# e-stop-radio.net
KiCad netlist of a schematic drawn in EAGLE
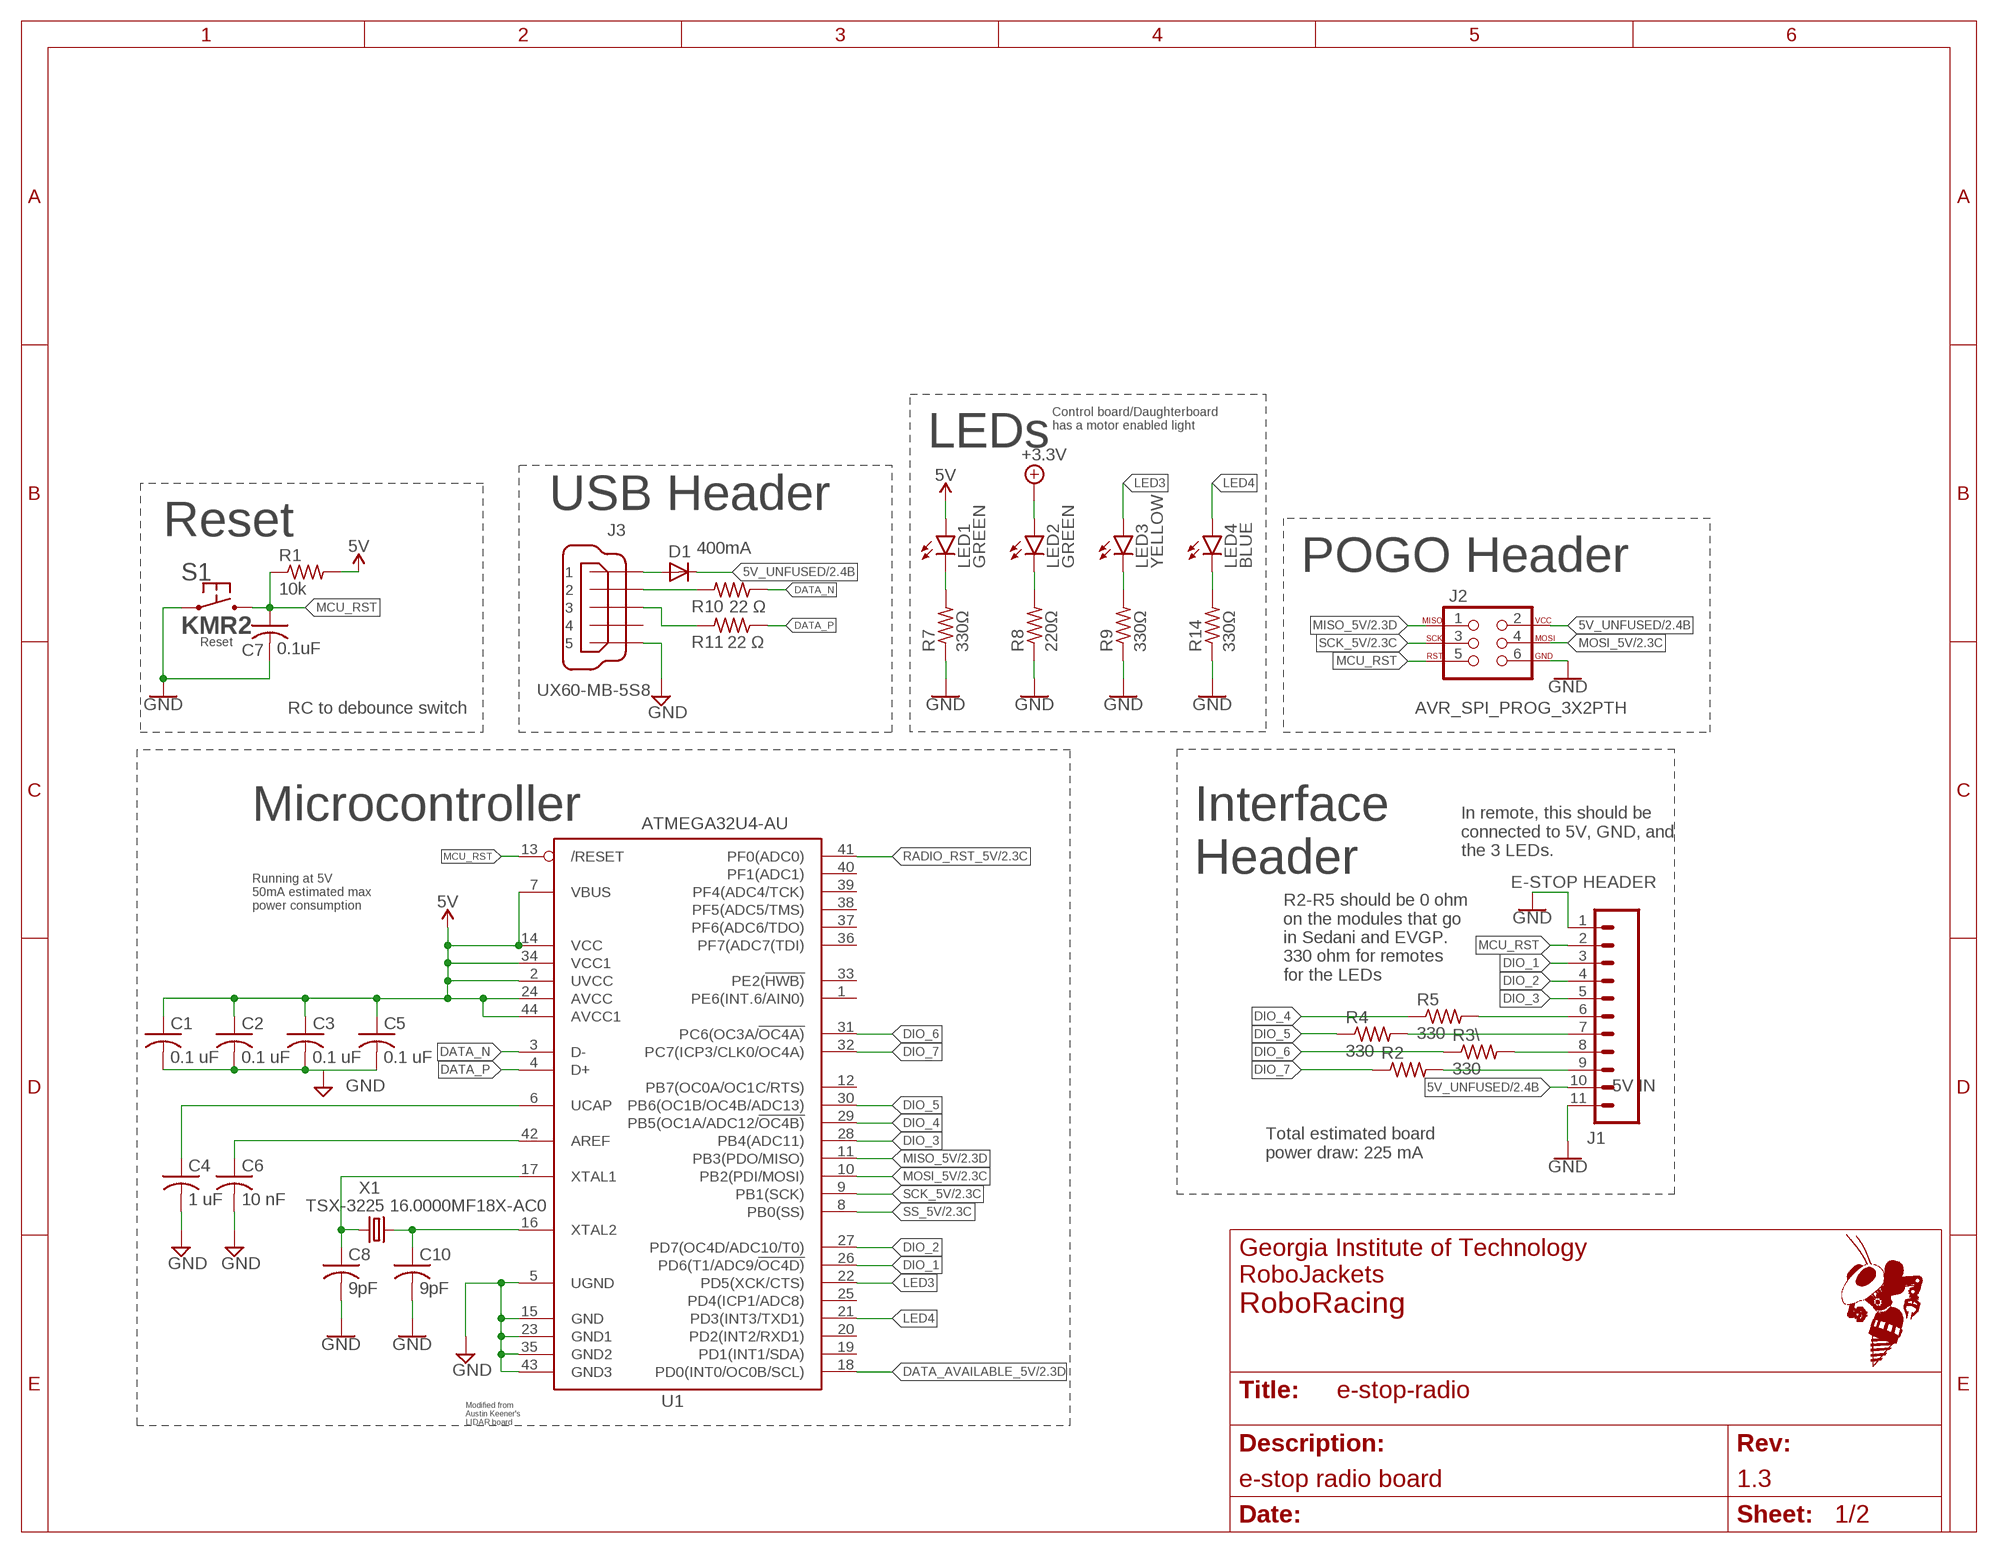
[diagram p0: schematic, sheet 1]
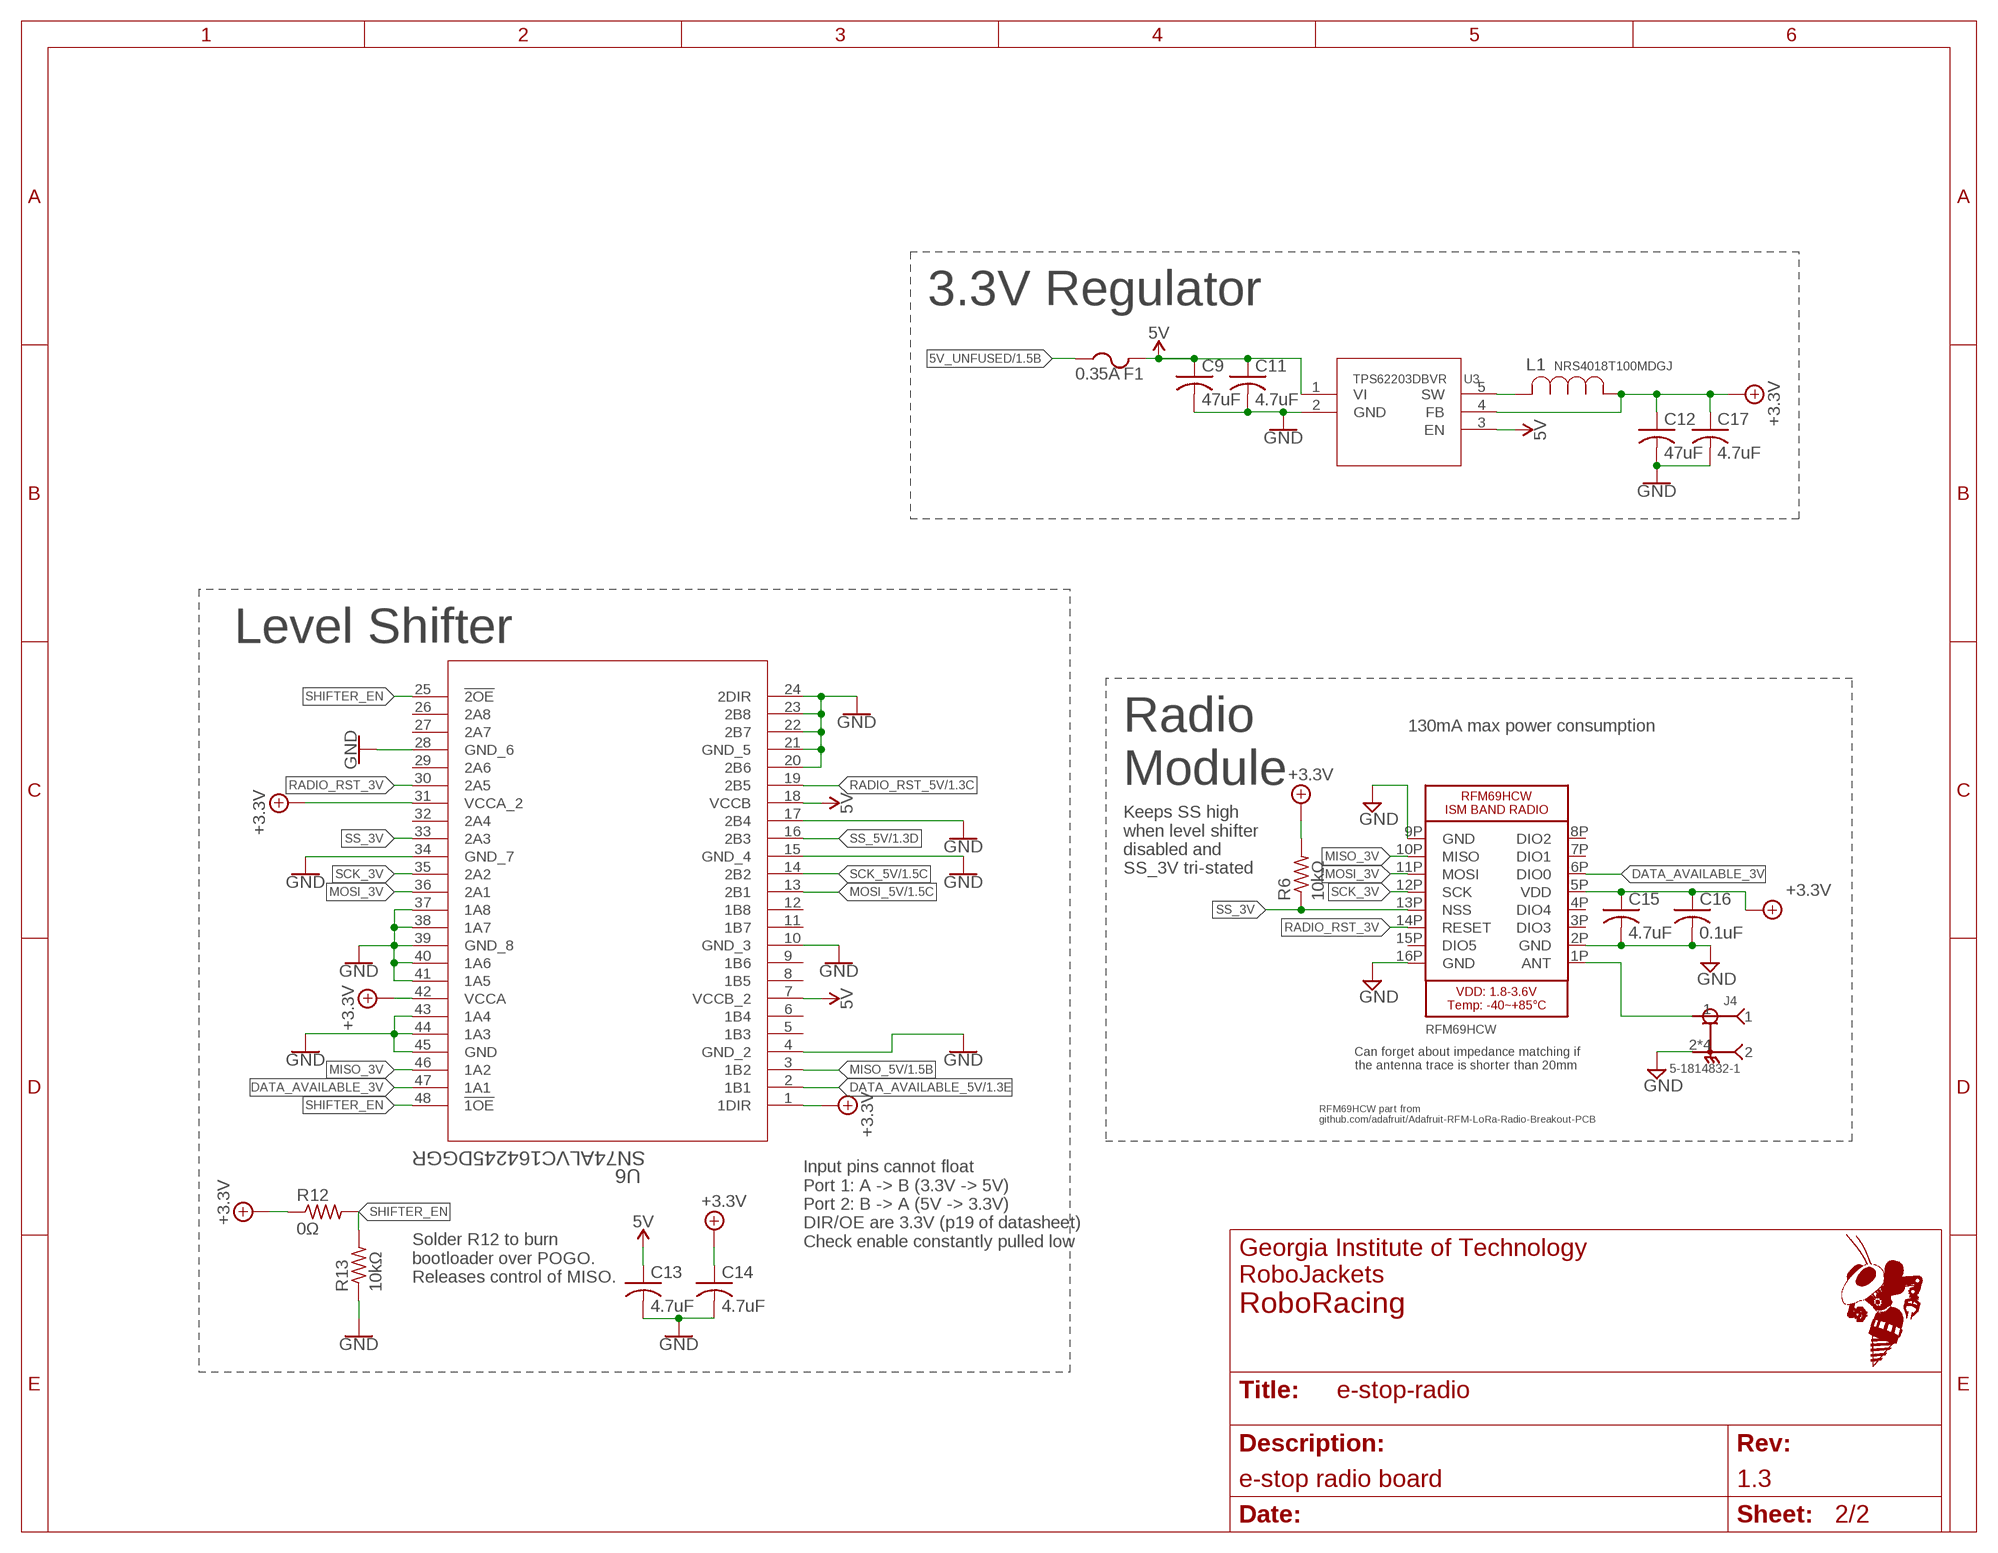
[diagram p1: schematic, sheet 2]

(export (version "E")
  (design (tool "Eeschema 10.0.6"))
  (components
    (comp (ref "C9")
      (value "47uF")
      (footprint "eagle-import:C1206")
      (libsource (lib "eagle-import") (part "C-USC1206"))
    )
    (comp (ref "C11")
      (value "4.7uF")
      (footprint "eagle-import:C0603")
      (libsource (lib "eagle-import") (part "C-USC0603"))
    )
    (comp (ref "C12")
      (value "47uF")
      (footprint "eagle-import:C1206")
      (libsource (lib "eagle-import") (part "C-USC1206"))
    )
    (comp (ref "C13")
      (value "4.7uF")
      (footprint "eagle-import:C0603")
      (libsource (lib "eagle-import") (part "C-USC0603"))
    )
    (comp (ref "C14")
      (value "4.7uF")
      (footprint "eagle-import:C0603")
      (libsource (lib "eagle-import") (part "C-USC0603"))
    )
    (comp (ref "C15")
      (value "4.7uF")
      (footprint "eagle-import:C0603")
      (libsource (lib "eagle-import") (part "C-USC0603"))
    )
    (comp (ref "C16")
      (value "0.1uF")
      (footprint "eagle-import:C0603")
      (libsource (lib "eagle-import") (part "C-USC0603"))
    )
    (comp (ref "C17")
      (value "4.7uF")
      (footprint "eagle-import:C0603")
      (libsource (lib "eagle-import") (part "C-USC0603"))
    )
    (comp (ref "F1")
      (value "0.35A")
      (footprint "eagle-import:R1206")
      (libsource (lib "eagle-import") (part "PTCFUSE-1206"))
    )
    (comp (ref "J4")
      (value "5-1814832-1")
      (footprint "eagle-import:TE_5-1814832-1")
      (fields (field (name "DIGI-KEY_PART_NUMBER") "A97594-ND") (field (name "MF") "TE Connectivity"))
      (libsource (lib "eagle-import") (part "5-1814832-1"))
    )
    (comp (ref "L1")
      (value "NRS4018T100MDGJ")
      (footprint "eagle-import:IND_TAIYO_NRS4018")
      (libsource (lib "eagle-import") (part "NRS4018T100MDGJ"))
    )
    (comp (ref "R6")
      (value "10kΩ")
      (footprint "eagle-import:R0603")
      (libsource (lib "eagle-import") (part "R-US_R0603"))
    )
    (comp (ref "R12")
      (value "0Ω")
      (footprint "eagle-import:R0603")
      (libsource (lib "eagle-import") (part "R-US_R0603"))
    )
    (comp (ref "R13")
      (value "10kΩ")
      (footprint "eagle-import:R0603")
      (libsource (lib "eagle-import") (part "R-US_R0603"))
    )
    (comp (ref "U3")
      (value "TPS62203DBVR")
      (footprint "eagle-import:DBV5")
      (libsource (lib "eagle-import") (part "TPS62203DBVR"))
    )
    (comp (ref "U5")
      (value "RFM69HCW")
      (footprint "eagle-import:RFMHCW_SMT")
      (libsource (lib "eagle-import") (part "RFM69HCW_SMT"))
    )
    (comp (ref "U6")
      (value "SN74ALVC164245DGGR")
      (footprint "eagle-import:DGG48")
      (libsource (lib "eagle-import") (part "SN74ALVC164245DGGR"))
    )
    (comp (ref "C1")
      (value "0.1 uF")
      (footprint "eagle-import:C0603")
      (libsource (lib "eagle-import") (part "resistor_348_C-USC0603"))
    )
    (comp (ref "C2")
      (value "0.1 uF")
      (footprint "eagle-import:C0603")
      (libsource (lib "eagle-import") (part "resistor_348_C-USC0603"))
    )
    (comp (ref "C3")
      (value "0.1 uF")
      (footprint "eagle-import:C0603")
      (libsource (lib "eagle-import") (part "resistor_348_C-USC0603"))
    )
    (comp (ref "C4")
      (value "1 uF")
      (footprint "eagle-import:C0603")
      (libsource (lib "eagle-import") (part "resistor_348_C-USC0603"))
    )
    (comp (ref "C5")
      (value "0.1 uF")
      (footprint "eagle-import:C0603")
      (libsource (lib "eagle-import") (part "resistor_348_C-USC0603"))
    )
    (comp (ref "C6")
      (value "10 nF")
      (footprint "eagle-import:C0603")
      (libsource (lib "eagle-import") (part "resistor_348_C-USC0603"))
    )
    (comp (ref "C7")
      (value "0.1uF")
      (footprint "eagle-import:C0603")
      (libsource (lib "eagle-import") (part "C-USC0603"))
    )
    (comp (ref "C8")
      (value "9pF")
      (footprint "eagle-import:C0603")
      (libsource (lib "eagle-import") (part "resistor_348_C-USC0603"))
    )
    (comp (ref "C10")
      (value "9pF")
      (footprint "eagle-import:C0603")
      (libsource (lib "eagle-import") (part "resistor_348_C-USC0603"))
    )
    (comp (ref "D1")
      (value "400mA")
      (footprint "eagle-import:SOD323-R")
      (libsource (lib "eagle-import") (part "DIODE-SOD323-R"))
    )
    (comp (ref "J1")
      (value "E-STOP HEADER")
      (footprint "eagle-import:1X11")
      (libsource (lib "eagle-import") (part "CONN_11"))
    )
    (comp (ref "J2")
      (value "AVR_SPI_PROG_3X2PTH")
      (footprint "eagle-import:2X3")
      (libsource (lib "eagle-import") (part "AVR_SPI_PROG_3X2PTH"))
    )
    (comp (ref "J3")
      (value "UX60-MB-5S8")
      (footprint "eagle-import:UX60-MB-5S8")
      (libsource (lib "eagle-import") (part "UX60-MB-5S?8"))
    )
    (comp (ref "LED1")
      (value "GREEN")
      (footprint "eagle-import:CHIP-LED0603")
      (libsource (lib "eagle-import") (part "LEDCHIP-LED0603"))
    )
    (comp (ref "LED2")
      (value "GREEN")
      (footprint "eagle-import:CHIP-LED0603")
      (libsource (lib "eagle-import") (part "LEDCHIP-LED0603"))
    )
    (comp (ref "LED3")
      (value "YELLOW")
      (footprint "eagle-import:CHIP-LED0603")
      (libsource (lib "eagle-import") (part "LEDCHIP-LED0603"))
    )
    (comp (ref "LED4")
      (value "BLUE")
      (footprint "eagle-import:CHIP-LED0603")
      (libsource (lib "eagle-import") (part "LEDCHIP-LED0603"))
    )
    (comp (ref "R1")
      (value "10k")
      (footprint "eagle-import:R0603")
      (libsource (lib "eagle-import") (part "R-US_R0603"))
    )
    (comp (ref "R2")
      (value "330")
      (footprint "eagle-import:R0603")
      (libsource (lib "eagle-import") (part "R-US_R0603"))
    )
    (comp (ref "R3\\")
      (value "330")
      (footprint "eagle-import:R0603")
      (libsource (lib "eagle-import") (part "R-US_R0603"))
    )
    (comp (ref "R4")
      (value "330")
      (footprint "eagle-import:R0603")
      (libsource (lib "eagle-import") (part "R-US_R0603"))
    )
    (comp (ref "R5")
      (value "330")
      (footprint "eagle-import:R0603")
      (libsource (lib "eagle-import") (part "R-US_R0603"))
    )
    (comp (ref "R7")
      (value "330Ω")
      (footprint "eagle-import:R0603")
      (libsource (lib "eagle-import") (part "R-US_R0603"))
    )
    (comp (ref "R8")
      (value "220Ω")
      (footprint "eagle-import:R0603")
      (libsource (lib "eagle-import") (part "R-US_R0603"))
    )
    (comp (ref "R9")
      (value "330Ω")
      (footprint "eagle-import:R0603")
      (libsource (lib "eagle-import") (part "R-US_R0603"))
    )
    (comp (ref "R10")
      (value "22 Ω")
      (footprint "eagle-import:R0603")
      (libsource (lib "eagle-import") (part "R-US_R0603"))
    )
    (comp (ref "R11")
      (value "22 Ω")
      (footprint "eagle-import:R0603")
      (libsource (lib "eagle-import") (part "R-US_R0603"))
    )
    (comp (ref "R14")
      (value "330Ω")
      (footprint "eagle-import:R0603")
      (libsource (lib "eagle-import") (part "R-US_R0603"))
    )
    (comp (ref "S1")
      (value "KMR2")
      (footprint "eagle-import:KMR2")
      (fields (field (name "FUNCTION") "Reset"))
      (libsource (lib "eagle-import") (part "KMR2"))
    )
    (comp (ref "U1")
      (value "ATMEGA32U4-AU")
      (footprint "eagle-import:TQFP44")
      (libsource (lib "eagle-import") (part "ATMEGA32U4-AU"))
    )
    (comp (ref "X1")
      (value "TSX-3225 16.0000MF18X-AC0")
      (footprint "eagle-import:XTAL-3.2X2.5")
      (libsource (lib "eagle-import") (part "XTAL-3.2X2.5"))
    )
  )
  (nets
    (net (code "1") (name "+3.3V") (class "Default")
      (node (ref "C12") (pin "1") (pinfunction "1_1") (pintype "passive"))
      (node (ref "C14") (pin "1") (pinfunction "1_1") (pintype "passive"))
      (node (ref "C15") (pin "1") (pinfunction "1_1") (pintype "passive"))
      (node (ref "C16") (pin "1") (pinfunction "1_1") (pintype "passive"))
      (node (ref "C17") (pin "1") (pinfunction "1_1") (pintype "passive"))
      (node (ref "L1") (pin "1") (pinfunction "1_1") (pintype "passive"))
      (node (ref "LED2") (pin "A") (pinfunction "A_A") (pintype "passive"))
      (node (ref "R12") (pin "1") (pinfunction "1_1") (pintype "passive"))
      (node (ref "R6") (pin "2") (pinfunction "2_2") (pintype "passive"))
      (node (ref "U3") (pin "4") (pinfunction "FB_4") (pintype "input"))
      (node (ref "U5") (pin "5P") (pinfunction "VDD_5P") (pintype "power_in"))
      (node (ref "U6") (pin "1") (pinfunction "1DIR_1") (pintype "input"))
      (node (ref "U6") (pin "31") (pinfunction "VCCA_2_31") (pintype "power_in"))
      (node (ref "U6") (pin "42") (pinfunction "VCCA_42") (pintype "power_in"))
    )
    (net (code "2") (name "5V") (class "Default")
      (node (ref "C1") (pin "1") (pinfunction "1_1") (pintype "passive"))
      (node (ref "C11") (pin "1") (pinfunction "1_1") (pintype "passive"))
      (node (ref "C13") (pin "1") (pinfunction "1_1") (pintype "passive"))
      (node (ref "C2") (pin "1") (pinfunction "1_1") (pintype "passive"))
      (node (ref "C3") (pin "1") (pinfunction "1_1") (pintype "passive"))
      (node (ref "C5") (pin "1") (pinfunction "1_1") (pintype "passive"))
      (node (ref "C9") (pin "1") (pinfunction "1_1") (pintype "passive"))
      (node (ref "F1") (pin "2") (pinfunction "2_2") (pintype "passive"))
      (node (ref "LED1") (pin "A") (pinfunction "A_A") (pintype "passive"))
      (node (ref "R1") (pin "2") (pinfunction "2_2") (pintype "passive"))
      (node (ref "U1") (pin "14") (pinfunction "VCC_14") (pintype "bidirectional"))
      (node (ref "U1") (pin "2") (pinfunction "UVCC_2") (pintype "bidirectional"))
      (node (ref "U1") (pin "24") (pinfunction "AVCC_24") (pintype "bidirectional"))
      (node (ref "U1") (pin "34") (pinfunction "VCC1_34") (pintype "bidirectional"))
      (node (ref "U1") (pin "44") (pinfunction "AVCC1_44") (pintype "bidirectional"))
      (node (ref "U1") (pin "7") (pinfunction "VBUS_7") (pintype "bidirectional"))
      (node (ref "U3") (pin "1") (pinfunction "VI_1") (pintype "input"))
      (node (ref "U3") (pin "3") (pinfunction "EN_3") (pintype "input"))
      (node (ref "U6") (pin "18") (pinfunction "VCCB_18") (pintype "power_in"))
      (node (ref "U6") (pin "7") (pinfunction "VCCB_2_7") (pintype "power_in"))
    )
    (net (code "3") (name "5V_UNFUSED") (class "Default")
      (node (ref "D1") (pin "C") (pinfunction "C_C") (pintype "passive"))
      (node (ref "F1") (pin "1") (pinfunction "1_1") (pintype "passive"))
      (node (ref "J1") (pin "10") (pinfunction "10_10") (pintype "passive"))
      (node (ref "J2") (pin "2") (pinfunction "2_2") (pintype "passive"))
    )
    (net (code "4") (name "DATA_AVAILABLE_3V") (class "Default")
      (node (ref "U5") (pin "6P") (pinfunction "DIO0_6P") (pintype "bidirectional"))
      (node (ref "U6") (pin "47") (pinfunction "1A1_47") (pintype "bidirectional"))
    )
    (net (code "5") (name "DATA_AVAILABLE_5V") (class "Default")
      (node (ref "U1") (pin "18") (pinfunction "PD0(INT0/OC0B/SCL)_18") (pintype "bidirectional"))
      (node (ref "U6") (pin "2") (pinfunction "1B1_2") (pintype "bidirectional"))
    )
    (net (code "6") (name "DATA_N") (class "Default")
      (node (ref "R10") (pin "1") (pinfunction "1_1") (pintype "passive"))
      (node (ref "U1") (pin "3") (pinfunction "D-_3") (pintype "bidirectional"))
    )
    (net (code "7") (name "DATA_P") (class "Default")
      (node (ref "R11") (pin "1") (pinfunction "1_1") (pintype "passive"))
      (node (ref "U1") (pin "4") (pinfunction "D+_4") (pintype "bidirectional"))
    )
    (net (code "8") (name "DIO_1") (class "Default")
      (node (ref "J1") (pin "3") (pinfunction "3_3") (pintype "passive"))
      (node (ref "U1") (pin "26") (pinfunction "PD6(T1/ADC9/~{OC4D})_26") (pintype "bidirectional"))
    )
    (net (code "9") (name "DIO_2") (class "Default")
      (node (ref "J1") (pin "4") (pinfunction "4_4") (pintype "passive"))
      (node (ref "U1") (pin "27") (pinfunction "PD7(OC4D/ADC10/T0)_27") (pintype "bidirectional"))
    )
    (net (code "10") (name "DIO_3") (class "Default")
      (node (ref "J1") (pin "5") (pinfunction "5_5") (pintype "passive"))
      (node (ref "U1") (pin "28") (pinfunction "PB4(ADC11)_28") (pintype "bidirectional"))
    )
    (net (code "11") (name "DIO_4") (class "Default")
      (node (ref "R5") (pin "1") (pinfunction "1_1") (pintype "passive"))
      (node (ref "U1") (pin "29") (pinfunction "PB5(OC1A/ADC12/~{OC4B})_29") (pintype "bidirectional"))
    )
    (net (code "12") (name "DIO_5") (class "Default")
      (node (ref "R4") (pin "1") (pinfunction "1_1") (pintype "passive"))
      (node (ref "U1") (pin "30") (pinfunction "PB6(OC1B/OC4B/ADC13)_30") (pintype "bidirectional"))
    )
    (net (code "13") (name "DIO_6") (class "Default")
      (node (ref "R3\\") (pin "1") (pinfunction "1_1") (pintype "passive"))
      (node (ref "U1") (pin "31") (pinfunction "PC6(OC3A/~{OC4A})_31") (pintype "bidirectional"))
    )
    (net (code "14") (name "DIO_7") (class "Default")
      (node (ref "R2") (pin "1") (pinfunction "1_1") (pintype "passive"))
      (node (ref "U1") (pin "32") (pinfunction "PC7(ICP3/CLK0/OC4A)_32") (pintype "bidirectional"))
    )
    (net (code "15") (name "GND") (class "Default")
      (node (ref "C1") (pin "2") (pinfunction "2_2") (pintype "passive"))
      (node (ref "C10") (pin "2") (pinfunction "2_2") (pintype "passive"))
      (node (ref "C11") (pin "2") (pinfunction "2_2") (pintype "passive"))
      (node (ref "C12") (pin "2") (pinfunction "2_2") (pintype "passive"))
      (node (ref "C13") (pin "2") (pinfunction "2_2") (pintype "passive"))
      (node (ref "C14") (pin "2") (pinfunction "2_2") (pintype "passive"))
      (node (ref "C15") (pin "2") (pinfunction "2_2") (pintype "passive"))
      (node (ref "C16") (pin "2") (pinfunction "2_2") (pintype "passive"))
      (node (ref "C17") (pin "2") (pinfunction "2_2") (pintype "passive"))
      (node (ref "C2") (pin "2") (pinfunction "2_2") (pintype "passive"))
      (node (ref "C3") (pin "2") (pinfunction "2_2") (pintype "passive"))
      (node (ref "C4") (pin "2") (pinfunction "2_2") (pintype "passive"))
      (node (ref "C5") (pin "2") (pinfunction "2_2") (pintype "passive"))
      (node (ref "C6") (pin "2") (pinfunction "2_2") (pintype "passive"))
      (node (ref "C7") (pin "2") (pinfunction "2_2") (pintype "passive"))
      (node (ref "C8") (pin "2") (pinfunction "2_2") (pintype "passive"))
      (node (ref "C9") (pin "2") (pinfunction "2_2") (pintype "passive"))
      (node (ref "J1") (pin "1") (pinfunction "1_1") (pintype "passive"))
      (node (ref "J1") (pin "11") (pinfunction "11_11") (pintype "passive"))
      (node (ref "J2") (pin "6") (pinfunction "6_6") (pintype "passive"))
      (node (ref "J3") (pin "5") (pinfunction "5_5") (pintype "passive"))
      (node (ref "J4") (pin "2") (pinfunction "2_2") (pintype "passive"))
      (node (ref "J4") (pin "3") (pinfunction "2_3") (pintype "passive"))
      (node (ref "J4") (pin "4") (pinfunction "2_4") (pintype "passive"))
      (node (ref "J4") (pin "5") (pinfunction "2_5") (pintype "passive"))
      (node (ref "R13") (pin "1") (pinfunction "1_1") (pintype "passive"))
      (node (ref "R14") (pin "1") (pinfunction "1_1") (pintype "passive"))
      (node (ref "R7") (pin "1") (pinfunction "1_1") (pintype "passive"))
      (node (ref "R8") (pin "1") (pinfunction "1_1") (pintype "passive"))
      (node (ref "R9") (pin "1") (pinfunction "1_1") (pintype "passive"))
      (node (ref "S1") (pin "1.1") (pinfunction "1_1.1") (pintype "passive"))
      (node (ref "S1") (pin "1.2") (pinfunction "1_1.2") (pintype "passive"))
      (node (ref "U1") (pin "15") (pinfunction "GND_15") (pintype "bidirectional"))
      (node (ref "U1") (pin "23") (pinfunction "GND1_23") (pintype "bidirectional"))
      (node (ref "U1") (pin "35") (pinfunction "GND2_35") (pintype "bidirectional"))
      (node (ref "U1") (pin "43") (pinfunction "GND3_43") (pintype "bidirectional"))
      (node (ref "U1") (pin "5") (pinfunction "UGND_5") (pintype "bidirectional"))
      (node (ref "U3") (pin "2") (pinfunction "GND_2") (pintype "power_in"))
      (node (ref "U5") (pin "16P") (pinfunction "GND_16P") (pintype "power_in"))
      (node (ref "U5") (pin "2P") (pinfunction "GND_2P") (pintype "power_in"))
      (node (ref "U5") (pin "9P") (pinfunction "GND_9P") (pintype "power_in"))
      (node (ref "U6") (pin "10") (pinfunction "GND_3_10") (pintype "power_in"))
      (node (ref "U6") (pin "15") (pinfunction "GND_4_15") (pintype "power_in"))
      (node (ref "U6") (pin "17") (pinfunction "2B4_17") (pintype "bidirectional"))
      (node (ref "U6") (pin "20") (pinfunction "2B6_20") (pintype "bidirectional"))
      (node (ref "U6") (pin "21") (pinfunction "GND_5_21") (pintype "power_in"))
      (node (ref "U6") (pin "22") (pinfunction "2B7_22") (pintype "bidirectional"))
      (node (ref "U6") (pin "23") (pinfunction "2B8_23") (pintype "bidirectional"))
      (node (ref "U6") (pin "24") (pinfunction "2DIR_24") (pintype "input"))
      (node (ref "U6") (pin "28") (pinfunction "GND_6_28") (pintype "power_in"))
      (node (ref "U6") (pin "34") (pinfunction "GND_7_34") (pintype "power_in"))
      (node (ref "U6") (pin "37") (pinfunction "1A8_37") (pintype "bidirectional"))
      (node (ref "U6") (pin "38") (pinfunction "1A7_38") (pintype "bidirectional"))
      (node (ref "U6") (pin "39") (pinfunction "GND_8_39") (pintype "power_in"))
      (node (ref "U6") (pin "4") (pinfunction "GND_2_4") (pintype "power_in"))
      (node (ref "U6") (pin "40") (pinfunction "1A6_40") (pintype "bidirectional"))
      (node (ref "U6") (pin "41") (pinfunction "1A5_41") (pintype "bidirectional"))
      (node (ref "U6") (pin "43") (pinfunction "1A4_43") (pintype "bidirectional"))
      (node (ref "U6") (pin "44") (pinfunction "1A3_44") (pintype "bidirectional"))
      (node (ref "U6") (pin "45") (pinfunction "GND_45") (pintype "power_in"))
    )
    (net (code "16") (name "LED3") (class "Default")
      (node (ref "LED3") (pin "A") (pinfunction "A_A") (pintype "passive"))
      (node (ref "U1") (pin "22") (pinfunction "PD5(XCK/CTS)_22") (pintype "bidirectional"))
    )
    (net (code "17") (name "LED4") (class "Default")
      (node (ref "LED4") (pin "A") (pinfunction "A_A") (pintype "passive"))
      (node (ref "U1") (pin "21") (pinfunction "PD3(INT3/TXD1)_21") (pintype "bidirectional"))
    )
    (net (code "18") (name "MCU_RST") (class "Default")
      (node (ref "C7") (pin "1") (pinfunction "1_1") (pintype "passive"))
      (node (ref "J1") (pin "2") (pinfunction "2_2") (pintype "passive"))
      (node (ref "J2") (pin "5") (pinfunction "5_5") (pintype "passive"))
      (node (ref "R1") (pin "1") (pinfunction "1_1") (pintype "passive"))
      (node (ref "S1") (pin "2.1") (pinfunction "2_2.1") (pintype "passive"))
      (node (ref "S1") (pin "2.2") (pinfunction "2_2.2") (pintype "passive"))
      (node (ref "U1") (pin "13") (pinfunction "/RESET_13") (pintype "bidirectional"))
    )
    (net (code "19") (name "MISO_3V") (class "Default")
      (node (ref "U5") (pin "10P") (pinfunction "MISO_10P") (pintype "output"))
      (node (ref "U6") (pin "46") (pinfunction "1A2_46") (pintype "bidirectional"))
    )
    (net (code "20") (name "MISO_5V") (class "Default")
      (node (ref "J2") (pin "1") (pinfunction "1_1") (pintype "passive"))
      (node (ref "U1") (pin "11") (pinfunction "PB3(PDO/MISO)_11") (pintype "bidirectional"))
      (node (ref "U6") (pin "3") (pinfunction "1B2_3") (pintype "bidirectional"))
    )
    (net (code "21") (name "MOSI_3V") (class "Default")
      (node (ref "U5") (pin "11P") (pinfunction "MOSI_11P") (pintype "input"))
      (node (ref "U6") (pin "36") (pinfunction "2A1_36") (pintype "bidirectional"))
    )
    (net (code "22") (name "MOSI_5V") (class "Default")
      (node (ref "J2") (pin "4") (pinfunction "4_4") (pintype "passive"))
      (node (ref "U1") (pin "10") (pinfunction "PB2(PDI/MOSI)_10") (pintype "bidirectional"))
      (node (ref "U6") (pin "13") (pinfunction "2B1_13") (pintype "bidirectional"))
    )
    (net (code "23") (name "Net-(D1-PadA)") (class "Default")
      (node (ref "D1") (pin "A") (pinfunction "A_A") (pintype "passive"))
      (node (ref "J3") (pin "1") (pinfunction "1_1") (pintype "passive"))
    )
    (net (code "24") (name "Net-(J1-Pad6)") (class "Default")
      (node (ref "J1") (pin "6") (pinfunction "6_6") (pintype "passive"))
      (node (ref "R5") (pin "2") (pinfunction "2_2") (pintype "passive"))
    )
    (net (code "25") (name "Net-(J1-Pad7)") (class "Default")
      (node (ref "J1") (pin "7") (pinfunction "7_7") (pintype "passive"))
      (node (ref "R4") (pin "2") (pinfunction "2_2") (pintype "passive"))
    )
    (net (code "26") (name "Net-(J1-Pad8)") (class "Default")
      (node (ref "J1") (pin "8") (pinfunction "8_8") (pintype "passive"))
      (node (ref "R3\\") (pin "2") (pinfunction "2_2") (pintype "passive"))
    )
    (net (code "27") (name "Net-(J1-Pad9)") (class "Default")
      (node (ref "J1") (pin "9") (pinfunction "9_9") (pintype "passive"))
      (node (ref "R2") (pin "2") (pinfunction "2_2") (pintype "passive"))
    )
    (net (code "28") (name "Net-(J3-Pad2)") (class "Default")
      (node (ref "J3") (pin "2") (pinfunction "2_2") (pintype "passive"))
      (node (ref "R10") (pin "2") (pinfunction "2_2") (pintype "passive"))
    )
    (net (code "29") (name "Net-(J3-Pad3)") (class "Default")
      (node (ref "J3") (pin "3") (pinfunction "3_3") (pintype "passive"))
      (node (ref "R11") (pin "2") (pinfunction "2_2") (pintype "passive"))
    )
    (net (code "30") (name "Net-(LED1-PadC)") (class "Default")
      (node (ref "LED1") (pin "C") (pinfunction "C_C") (pintype "passive"))
      (node (ref "R7") (pin "2") (pinfunction "2_2") (pintype "passive"))
    )
    (net (code "31") (name "Net-(LED2-PadC)") (class "Default")
      (node (ref "LED2") (pin "C") (pinfunction "C_C") (pintype "passive"))
      (node (ref "R8") (pin "2") (pinfunction "2_2") (pintype "passive"))
    )
    (net (code "32") (name "Net-(LED3-PadC)") (class "Default")
      (node (ref "LED3") (pin "C") (pinfunction "C_C") (pintype "passive"))
      (node (ref "R9") (pin "2") (pinfunction "2_2") (pintype "passive"))
    )
    (net (code "33") (name "Net-(LED4-PadC)") (class "Default")
      (node (ref "LED4") (pin "C") (pinfunction "C_C") (pintype "passive"))
      (node (ref "R14") (pin "2") (pinfunction "2_2") (pintype "passive"))
    )
    (net (code "34") (name "Net-(U1-AREF)") (class "Default")
      (node (ref "C6") (pin "1") (pinfunction "1_1") (pintype "passive"))
      (node (ref "U1") (pin "42") (pinfunction "AREF_42") (pintype "bidirectional"))
    )
    (net (code "35") (name "Net-(U1-UCAP)") (class "Default")
      (node (ref "C4") (pin "1") (pinfunction "1_1") (pintype "passive"))
      (node (ref "U1") (pin "6") (pinfunction "UCAP_6") (pintype "bidirectional"))
    )
    (net (code "36") (name "Net-(U1-XTAL1)") (class "Default")
      (node (ref "C8") (pin "1") (pinfunction "1_1") (pintype "passive"))
      (node (ref "U1") (pin "17") (pinfunction "XTAL1_17") (pintype "bidirectional"))
      (node (ref "X1") (pin "1") (pinfunction "1_1") (pintype "passive"))
    )
    (net (code "37") (name "Net-(U1-XTAL2)") (class "Default")
      (node (ref "C10") (pin "1") (pinfunction "1_1") (pintype "passive"))
      (node (ref "U1") (pin "16") (pinfunction "XTAL2_16") (pintype "bidirectional"))
      (node (ref "X1") (pin "3") (pinfunction "2_3") (pintype "passive"))
    )
    (net (code "38") (name "Net-(U3-SW)") (class "Default")
      (node (ref "L1") (pin "2") (pinfunction "2_2") (pintype "passive"))
      (node (ref "U3") (pin "5") (pinfunction "SW_5") (pintype "bidirectional"))
    )
    (net (code "39") (name "Net-(U5-ANT)") (class "Default")
      (node (ref "J4") (pin "1") (pinfunction "1_1") (pintype "passive"))
      (node (ref "U5") (pin "1P") (pinfunction "ANT_1P") (pintype "bidirectional"))
    )
    (net (code "40") (name "RADIO_RST_3V") (class "Default")
      (node (ref "U5") (pin "14P") (pinfunction "RESET_14P") (pintype "input"))
      (node (ref "U6") (pin "30") (pinfunction "2A5_30") (pintype "bidirectional"))
    )
    (net (code "41") (name "RADIO_RST_5V") (class "Default")
      (node (ref "U1") (pin "41") (pinfunction "PF0(ADC0)_41") (pintype "bidirectional"))
      (node (ref "U6") (pin "19") (pinfunction "2B5_19") (pintype "bidirectional"))
    )
    (net (code "42") (name "SCK_3V") (class "Default")
      (node (ref "U5") (pin "12P") (pinfunction "SCK_12P") (pintype "input"))
      (node (ref "U6") (pin "35") (pinfunction "2A2_35") (pintype "bidirectional"))
    )
    (net (code "43") (name "SCK_5V") (class "Default")
      (node (ref "J2") (pin "3") (pinfunction "3_3") (pintype "passive"))
      (node (ref "U1") (pin "9") (pinfunction "PB1(SCK)_9") (pintype "bidirectional"))
      (node (ref "U6") (pin "14") (pinfunction "2B2_14") (pintype "bidirectional"))
    )
    (net (code "44") (name "SHIFTER_EN") (class "Default")
      (node (ref "R12") (pin "2") (pinfunction "2_2") (pintype "passive"))
      (node (ref "R13") (pin "2") (pinfunction "2_2") (pintype "passive"))
      (node (ref "U6") (pin "25") (pinfunction "~{2OE}_25") (pintype "input"))
      (node (ref "U6") (pin "48") (pinfunction "~{1OE}_48") (pintype "input"))
    )
    (net (code "45") (name "SS_3V") (class "Default")
      (node (ref "R6") (pin "1") (pinfunction "1_1") (pintype "passive"))
      (node (ref "U5") (pin "13P") (pinfunction "NSS_13P") (pintype "input"))
      (node (ref "U6") (pin "33") (pinfunction "2A3_33") (pintype "bidirectional"))
    )
    (net (code "46") (name "SS_5V") (class "Default")
      (node (ref "U1") (pin "8") (pinfunction "PB0(SS)_8") (pintype "bidirectional"))
      (node (ref "U6") (pin "16") (pinfunction "2B3_16") (pintype "bidirectional"))
    )
    (net (code "47") (name "unconnected-(J3-Pad4)") (class "Default")
      (node (ref "J3") (pin "4") (pinfunction "4_4") (pintype "passive"))
    )
    (net (code "48") (name "unconnected-(U1-PB7(OC0A{slash}OC1C{slash}RTS)-Pad12)") (class "Default")
      (node (ref "U1") (pin "12") (pinfunction "PB7(OC0A/OC1C/RTS)_12") (pintype "bidirectional"))
    )
    (net (code "49") (name "unconnected-(U1-PD1(INT1{slash}SDA)-Pad19)") (class "Default")
      (node (ref "U1") (pin "19") (pinfunction "PD1(INT1/SDA)_19") (pintype "bidirectional"))
    )
    (net (code "50") (name "unconnected-(U1-PD2(INT2{slash}RXD1)-Pad20)") (class "Default")
      (node (ref "U1") (pin "20") (pinfunction "PD2(INT2/RXD1)_20") (pintype "bidirectional"))
    )
    (net (code "51") (name "unconnected-(U1-PD4(ICP1{slash}ADC8)-Pad25)") (class "Default")
      (node (ref "U1") (pin "25") (pinfunction "PD4(ICP1/ADC8)_25") (pintype "bidirectional"))
    )
    (net (code "52") (name "unconnected-(U1-PE2(~{HWB})-Pad33)") (class "Default")
      (node (ref "U1") (pin "33") (pinfunction "PE2(~{HWB})_33") (pintype "bidirectional"))
    )
    (net (code "53") (name "unconnected-(U1-PE6(INT.6{slash}AIN0)-Pad1)") (class "Default")
      (node (ref "U1") (pin "1") (pinfunction "PE6(INT.6/AIN0)_1") (pintype "bidirectional"))
    )
    (net (code "54") (name "unconnected-(U1-PF1(ADC1)-Pad40)") (class "Default")
      (node (ref "U1") (pin "40") (pinfunction "PF1(ADC1)_40") (pintype "bidirectional"))
    )
    (net (code "55") (name "unconnected-(U1-PF4(ADC4{slash}TCK)-Pad39)") (class "Default")
      (node (ref "U1") (pin "39") (pinfunction "PF4(ADC4/TCK)_39") (pintype "bidirectional"))
    )
    (net (code "56") (name "unconnected-(U1-PF5(ADC5{slash}TMS)-Pad38)") (class "Default")
      (node (ref "U1") (pin "38") (pinfunction "PF5(ADC5/TMS)_38") (pintype "bidirectional"))
    )
    (net (code "57") (name "unconnected-(U1-PF6(ADC6{slash}TDO)-Pad37)") (class "Default")
      (node (ref "U1") (pin "37") (pinfunction "PF6(ADC6/TDO)_37") (pintype "bidirectional"))
    )
    (net (code "58") (name "unconnected-(U1-PF7(ADC7(TDI)-Pad36)") (class "Default")
      (node (ref "U1") (pin "36") (pinfunction "PF7(ADC7(TDI)_36") (pintype "bidirectional"))
    )
    (net (code "59") (name "unconnected-(U5-DIO1-Pad7P)") (class "Default")
      (node (ref "U5") (pin "7P") (pinfunction "DIO1_7P") (pintype "bidirectional"))
    )
    (net (code "60") (name "unconnected-(U5-DIO2-Pad8P)") (class "Default")
      (node (ref "U5") (pin "8P") (pinfunction "DIO2_8P") (pintype "bidirectional"))
    )
    (net (code "61") (name "unconnected-(U5-DIO3-Pad3P)") (class "Default")
      (node (ref "U5") (pin "3P") (pinfunction "DIO3_3P") (pintype "bidirectional"))
    )
    (net (code "62") (name "unconnected-(U5-DIO4-Pad4P)") (class "Default")
      (node (ref "U5") (pin "4P") (pinfunction "DIO4_4P") (pintype "bidirectional"))
    )
    (net (code "63") (name "unconnected-(U5-DIO5-Pad15P)") (class "Default")
      (node (ref "U5") (pin "15P") (pinfunction "DIO5_15P") (pintype "bidirectional"))
    )
    (net (code "64") (name "unconnected-(U6-1B3-Pad5)") (class "Default")
      (node (ref "U6") (pin "5") (pinfunction "1B3_5") (pintype "bidirectional"))
    )
    (net (code "65") (name "unconnected-(U6-1B4-Pad6)") (class "Default")
      (node (ref "U6") (pin "6") (pinfunction "1B4_6") (pintype "bidirectional"))
    )
    (net (code "66") (name "unconnected-(U6-1B5-Pad8)") (class "Default")
      (node (ref "U6") (pin "8") (pinfunction "1B5_8") (pintype "bidirectional"))
    )
    (net (code "67") (name "unconnected-(U6-1B6-Pad9)") (class "Default")
      (node (ref "U6") (pin "9") (pinfunction "1B6_9") (pintype "bidirectional"))
    )
    (net (code "68") (name "unconnected-(U6-1B7-Pad11)") (class "Default")
      (node (ref "U6") (pin "11") (pinfunction "1B7_11") (pintype "bidirectional"))
    )
    (net (code "69") (name "unconnected-(U6-1B8-Pad12)") (class "Default")
      (node (ref "U6") (pin "12") (pinfunction "1B8_12") (pintype "bidirectional"))
    )
    (net (code "70") (name "unconnected-(U6-2A4-Pad32)") (class "Default")
      (node (ref "U6") (pin "32") (pinfunction "2A4_32") (pintype "bidirectional"))
    )
    (net (code "71") (name "unconnected-(U6-2A6-Pad29)") (class "Default")
      (node (ref "U6") (pin "29") (pinfunction "2A6_29") (pintype "bidirectional"))
    )
    (net (code "72") (name "unconnected-(U6-2A7-Pad27)") (class "Default")
      (node (ref "U6") (pin "27") (pinfunction "2A7_27") (pintype "bidirectional"))
    )
    (net (code "73") (name "unconnected-(U6-2A8-Pad26)") (class "Default")
      (node (ref "U6") (pin "26") (pinfunction "2A8_26") (pintype "bidirectional"))
    )
  )
)
